# airDrums.net
KiCad netlist of a schematic drawn in Altium Designer
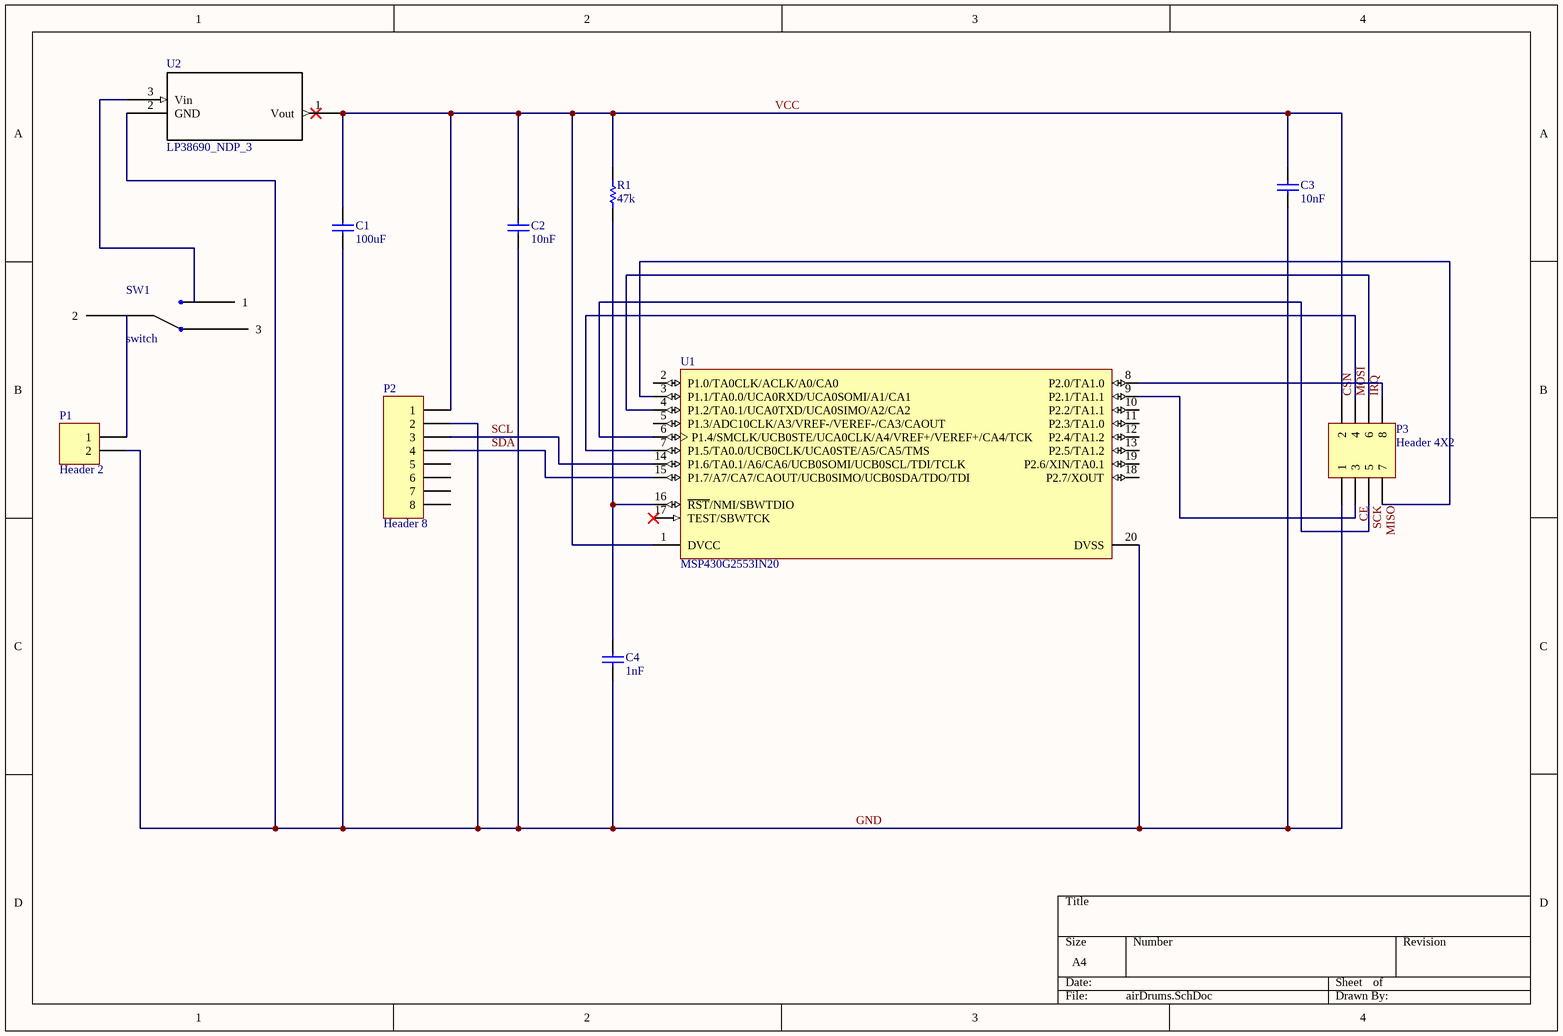
[diagram p0: airDrums.SchDoc]

(export (version "E")
  (design (tool "Eeschema 10.0.6"))
  (components
    (comp (ref "C1")
      (value "100uF")
      (footprint "CAPC6032X28N")
      (description "Capacitor (Semiconductor SIM Model)")
      (fields (field (name "PUBLISHER") "Altium Limited"))
      (libsource (lib "Miscellaneous Devices2") (part "Cap Semi"))
    )
    (comp (ref "C2")
      (value "10nF")
      (footprint "CAP0805")
      (description "Capacitor (Semiconductor SIM Model)")
      (fields (field (name "PUBLISHER") "Altium Limited"))
      (libsource (lib "Miscellaneous Devices2") (part "Cap Semi"))
    )
    (comp (ref "C3")
      (value "10nF")
      (footprint "CAP0805")
      (description "Capacitor (Semiconductor SIM Model)")
      (fields (field (name "PUBLISHER") "Altium Limited"))
      (libsource (lib "Miscellaneous Devices2") (part "Cap Semi"))
    )
    (comp (ref "C4")
      (value "1nF")
      (footprint "CAP0805")
      (description "Capacitor (Semiconductor SIM Model)")
      (fields (field (name "PUBLISHER") "Altium Limited"))
      (libsource (lib "Miscellaneous Devices2") (part "Cap Semi"))
    )
    (comp (ref "P1")
      (value "Header 2")
      (footprint "HDR1X2")
      (description "Header, 2-Pin")
      (fields (field (name "PUBLISHER") "Altium Limited"))
      (libsource (lib "Miscellaneous Connectors") (part "Header 2"))
    )
    (comp (ref "P2")
      (value "Header 8")
      (footprint "HDR1X8")
      (description "Header, 8-Pin")
      (fields (field (name "PUBLISHER") "Altium Limited"))
      (libsource (lib "Miscellaneous Connectors") (part "Header 8"))
    )
    (comp (ref "P3")
      (value "Header 4X2")
      (footprint "HDR2X4")
      (description "Header, 4-Pin, Dual row")
      (fields (field (name "PUBLISHER") "Altium Limited"))
      (libsource (lib "Miscellaneous Connectors") (part "Header 4X2"))
    )
    (comp (ref "R1")
      (value "47k")
      (footprint "CAP0805")
      (description "Semiconductor Resistor")
      (fields (field (name "PUBLISHER") "Altium Limited"))
      (libsource (lib "Miscellaneous Devices2") (part "Res Semi"))
    )
    (comp (ref "SW1") (value "switch") (footprint "Switch") (libsource (lib "mpu6050") (part "switch")))
    (comp (ref "U1")
      (value "MSP430G2553IN20")
      (footprint "TI-N20")
      (fields (field (name "MANUFACTURER") "Texas Instruments"))
      (libsource (lib "TI Microcontroller MSP430 16-bit Ultra-Low Power") (part "MSP430G2553IN20"))
    )
    (comp (ref "U2")
      (value "LP38690_NDP_3")
      (footprint "TD03B")
      (description "Imported")
      (fields (field (name "PARTNUMBER") "LP38690DT-18"))
      (libsource (lib "TI_LP38690") (part "LP38690_NDP_3"))
    )
  )
  (nets
    (net (code "1") (name "/CE") (class "Default")
      (node (ref "P3") (pin "3") (pinfunction "3_3") (pintype "passive"))
      (node (ref "U1") (pin "9") (pinfunction "P2.1/TA1.1_9") (pintype "bidirectional"))
    )
    (net (code "2") (name "/CSN") (class "Default")
      (node (ref "P3") (pin "4") (pinfunction "4_4") (pintype "passive"))
      (node (ref "U1") (pin "7") (pinfunction "P1.5/TA0.0/UCB0CLK/UCA0STE/A5/CA5/TMS_7") (pintype "bidirectional"))
    )
    (net (code "3") (name "/GND") (class "Default")
      (node (ref "C1") (pin "1") (pinfunction "1_1") (pintype "passive"))
      (node (ref "C2") (pin "1") (pinfunction "1_1") (pintype "passive"))
      (node (ref "C3") (pin "1") (pinfunction "1_1") (pintype "passive"))
      (node (ref "C4") (pin "1") (pinfunction "1_1") (pintype "passive"))
      (node (ref "P1") (pin "2") (pinfunction "2_2") (pintype "passive"))
      (node (ref "P2") (pin "2") (pinfunction "2_2") (pintype "passive"))
      (node (ref "P3") (pin "1") (pinfunction "1_1") (pintype "passive"))
      (node (ref "U1") (pin "20") (pinfunction "DVSS_20") (pintype "power_in"))
      (node (ref "U2") (pin "2") (pinfunction "GND_2") (pintype "passive"))
    )
    (net (code "4") (name "/IRQ") (class "Default")
      (node (ref "P3") (pin "8") (pinfunction "8_8") (pintype "passive"))
      (node (ref "U1") (pin "8") (pinfunction "P2.0/TA1.0_8") (pintype "bidirectional"))
    )
    (net (code "5") (name "/MISO") (class "Default")
      (node (ref "P3") (pin "7") (pinfunction "7_7") (pintype "passive"))
      (node (ref "U1") (pin "3") (pinfunction "P1.1/TA0.0/UCA0RXD/UCA0SOMI/A1/CA1_3") (pintype "bidirectional"))
    )
    (net (code "6") (name "/MOSI") (class "Default")
      (node (ref "P3") (pin "6") (pinfunction "6_6") (pintype "passive"))
      (node (ref "U1") (pin "4") (pinfunction "P1.2/TA0.1/UCA0TXD/UCA0SIMO/A2/CA2_4") (pintype "bidirectional"))
    )
    (net (code "7") (name "/SCK") (class "Default")
      (node (ref "P3") (pin "5") (pinfunction "5_5") (pintype "passive"))
      (node (ref "U1") (pin "6") (pinfunction "P1.4/SMCLK/UCB0STE/UCA0CLK/A4/VREF+/VEREF+/CA4/TCK_6") (pintype "bidirectional"))
    )
    (net (code "8") (name "/SCL") (class "Default")
      (node (ref "P2") (pin "3") (pinfunction "3_3") (pintype "passive"))
      (node (ref "U1") (pin "14") (pinfunction "P1.6/TA0.1/A6/CA6/UCB0SOMI/UCB0SCL/TDI/TCLK_14") (pintype "bidirectional"))
    )
    (net (code "9") (name "/SDA") (class "Default")
      (node (ref "P2") (pin "4") (pinfunction "4_4") (pintype "passive"))
      (node (ref "U1") (pin "15") (pinfunction "P1.7/A7/CA7/CAOUT/UCB0SIMO/UCB0SDA/TDO/TDI_15") (pintype "bidirectional"))
    )
    (net (code "10") (name "/VCC") (class "Default")
      (node (ref "C1") (pin "2") (pinfunction "2_2") (pintype "passive"))
      (node (ref "C2") (pin "2") (pinfunction "2_2") (pintype "passive"))
      (node (ref "C3") (pin "2") (pinfunction "2_2") (pintype "passive"))
      (node (ref "P2") (pin "1") (pinfunction "1_1") (pintype "passive"))
      (node (ref "P3") (pin "2") (pinfunction "2_2") (pintype "passive"))
      (node (ref "R1") (pin "2") (pinfunction "2_2") (pintype "passive"))
      (node (ref "U1") (pin "1") (pinfunction "DVCC_1") (pintype "power_in"))
      (node (ref "U2") (pin "1") (pinfunction "Vout_1") (pintype "output"))
    )
    (net (code "11") (name "Net-(P1-Pad1)") (class "Default")
      (node (ref "P1") (pin "1") (pinfunction "1_1") (pintype "passive"))
      (node (ref "SW1") (pin "2") (pinfunction "2_2") (pintype "passive"))
    )
    (net (code "12") (name "Net-(U1-~{RST}{slash}NMI{slash}SBWTDIO)") (class "Default")
      (node (ref "C4") (pin "2") (pinfunction "2_2") (pintype "passive"))
      (node (ref "R1") (pin "1") (pinfunction "1_1") (pintype "passive"))
      (node (ref "U1") (pin "16") (pinfunction "~{RST}/NMI/SBWTDIO_16") (pintype "bidirectional"))
    )
    (net (code "13") (name "Net-(U2-Vin)") (class "Default")
      (node (ref "SW1") (pin "1") (pinfunction "1_1") (pintype "passive"))
      (node (ref "U2") (pin "3") (pinfunction "Vin_3") (pintype "input"))
    )
    (net (code "14") (name "unconnected-(P2-Pad5)") (class "Default")
      (node (ref "P2") (pin "5") (pinfunction "5_5") (pintype "passive"))
    )
    (net (code "15") (name "unconnected-(P2-Pad6)") (class "Default")
      (node (ref "P2") (pin "6") (pinfunction "6_6") (pintype "passive"))
    )
    (net (code "16") (name "unconnected-(P2-Pad7)") (class "Default")
      (node (ref "P2") (pin "7") (pinfunction "7_7") (pintype "passive"))
    )
    (net (code "17") (name "unconnected-(P2-Pad8)") (class "Default")
      (node (ref "P2") (pin "8") (pinfunction "8_8") (pintype "passive"))
    )
    (net (code "18") (name "unconnected-(SW1-Pad3)") (class "Default")
      (node (ref "SW1") (pin "3") (pinfunction "3_3") (pintype "passive"))
    )
    (net (code "19") (name "unconnected-(U1-P1.0{slash}TA0CLK{slash}ACLK{slash}A0{slash}CA0-Pad2)") (class "Default")
      (node (ref "U1") (pin "2") (pinfunction "P1.0/TA0CLK/ACLK/A0/CA0_2") (pintype "bidirectional"))
    )
    (net (code "20") (name "unconnected-(U1-P1.3{slash}ADC10CLK{slash}A3{slash}VREF-{slash}VEREF-{slash}CA3{slash}CAOUT-Pad5)") (class "Default")
      (node (ref "U1") (pin "5") (pinfunction "P1.3/ADC10CLK/A3/VREF-/VEREF-/CA3/CAOUT_5") (pintype "bidirectional"))
    )
    (net (code "21") (name "unconnected-(U1-P2.2{slash}TA1.1-Pad10)") (class "Default")
      (node (ref "U1") (pin "10") (pinfunction "P2.2/TA1.1_10") (pintype "bidirectional"))
    )
    (net (code "22") (name "unconnected-(U1-P2.3{slash}TA1.0-Pad11)") (class "Default")
      (node (ref "U1") (pin "11") (pinfunction "P2.3/TA1.0_11") (pintype "bidirectional"))
    )
    (net (code "23") (name "unconnected-(U1-P2.4{slash}TA1.2-Pad12)") (class "Default")
      (node (ref "U1") (pin "12") (pinfunction "P2.4/TA1.2_12") (pintype "bidirectional"))
    )
    (net (code "24") (name "unconnected-(U1-P2.5{slash}TA1.2-Pad13)") (class "Default")
      (node (ref "U1") (pin "13") (pinfunction "P2.5/TA1.2_13") (pintype "bidirectional"))
    )
    (net (code "25") (name "unconnected-(U1-P2.6{slash}XIN{slash}TA0.1-Pad19)") (class "Default")
      (node (ref "U1") (pin "19") (pinfunction "P2.6/XIN/TA0.1_19") (pintype "bidirectional"))
    )
    (net (code "26") (name "unconnected-(U1-P2.7{slash}XOUT-Pad18)") (class "Default")
      (node (ref "U1") (pin "18") (pinfunction "P2.7/XOUT_18") (pintype "bidirectional"))
    )
    (net (code "27") (name "unconnected-(U1-TEST{slash}SBWTCK-Pad17)") (class "Default")
      (node (ref "U1") (pin "17") (pinfunction "TEST/SBWTCK_17") (pintype "input+no_connect"))
    )
  )
)
